# Nrf2460_1.net
KiCad netlist of a schematic drawn in Altium Designer
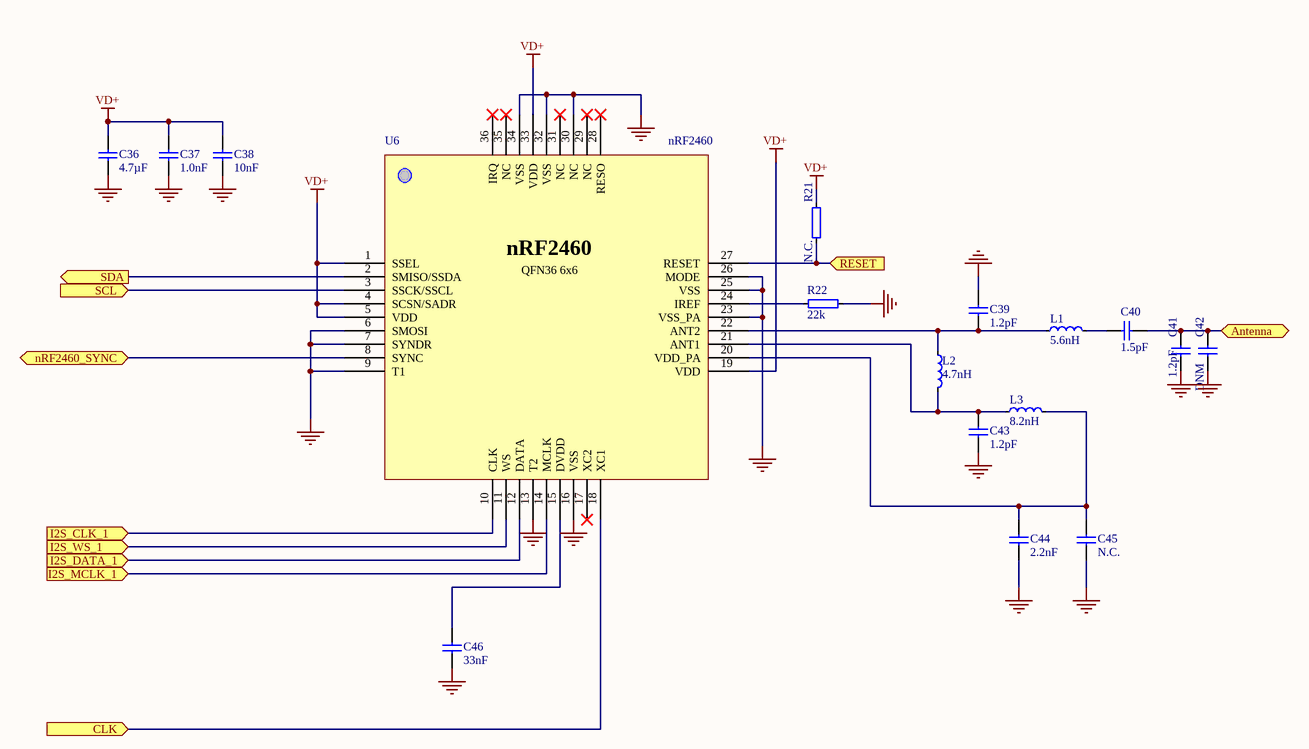
[diagram p0: Nrf2460_1.SchDoc]

(export (version "E")
  (design (tool "Eeschema 10.0.6"))
  (components
    (comp (ref "C36")
      (value "4.7µF")
      (footprint "0805")
      (description "Chip Cap 0805")
      (fields (field (name "PART NUMBER") "C0805-4µ7") (field (name "PUBLISHER") "Nordic Semiconductor"))
      (libsource (lib "Nordic Passive DB") (part "CAP"))
    )
    (comp (ref "C37")
      (value "1.0nF")
      (footprint "0402s")
      (description "Chip Cap 0402")
      (fields (field (name "PART NUMBER") "C0402-1n0") (field (name "PUBLISHER") "Nordic Semiconductor"))
      (libsource (lib "Nordic Passive DB") (part "CAP"))
    )
    (comp (ref "C38")
      (value "10nF")
      (footprint "0402s")
      (description "Chip Cap 0402")
      (fields (field (name "PART NUMBER") "C0402-10n") (field (name "PUBLISHER") "Nordic Semiconductor"))
      (libsource (lib "Nordic Passive DB") (part "CAP"))
    )
    (comp (ref "C39")
      (value "1.2pF")
      (footprint "0402s")
      (description "Chip Cap 0402")
      (fields (field (name "PART NUMBER") "C0402-1.2p") (field (name "PUBLISHER") "Nordic Semiconductor"))
      (libsource (lib "Nordic Passive DB") (part "CAP"))
    )
    (comp (ref "C40")
      (value "1.5pF")
      (footprint "0402s")
      (description "Chip Cap 0402")
      (fields (field (name "PART NUMBER") "C0402-1.5p") (field (name "PUBLISHER") "Nordic Semiconductor"))
      (libsource (lib "Nordic Passive DB") (part "CAP"))
    )
    (comp (ref "C41")
      (value "1.2pF")
      (footprint "0402s")
      (description "Chip Cap 0402")
      (fields (field (name "PART NUMBER") "C0402-1.2p") (field (name "PUBLISHER") "Nordic Semiconductor"))
      (libsource (lib "Nordic Passive DB") (part "CAP"))
    )
    (comp (ref "C42")
      (value "DNM")
      (footprint "0402s")
      (description "Chip Cap 0402")
      (fields (field (name "PART NUMBER") "C0402-1.2p") (field (name "PUBLISHER") "Nordic Semiconductor"))
      (libsource (lib "Nordic Passive DB") (part "CAP"))
    )
    (comp (ref "C43")
      (value "1.2pF")
      (footprint "0402s")
      (description "Chip Cap 0402")
      (fields (field (name "PART NUMBER") "C0402-1.2p") (field (name "PUBLISHER") "Nordic Semiconductor"))
      (libsource (lib "Nordic Passive DB") (part "CAP"))
    )
    (comp (ref "C44")
      (value "2.2nF")
      (footprint "0402s")
      (description "Chip Cap 0402")
      (fields (field (name "PART NUMBER") "C0402-2n2") (field (name "PUBLISHER") "Nordic Semiconductor"))
      (libsource (lib "Nordic Passive DB") (part "CAP"))
    )
    (comp (ref "C45")
      (value "N.C.")
      (footprint "0402s")
      (description "Chip Cap 0402")
      (fields (field (name "PART NUMBER") "C0402-N.C.") (field (name "PUBLISHER") "Nordic Semiconductor"))
      (libsource (lib "Nordic Passive DB") (part "CAP_NO_BOM"))
    )
    (comp (ref "C46")
      (value "33nF")
      (footprint "0402s")
      (description "Chip Cap 0402")
      (fields (field (name "PART NUMBER") "C0402-33n") (field (name "PUBLISHER") "Nordic Semiconductor"))
      (libsource (lib "Nordic Passive DB") (part "CAP"))
    )
    (comp (ref "L1")
      (value "5.6nH")
      (footprint "0402s")
      (description "Chip Ind 0402")
      (fields
        (field (name "PART NUMBER") "L0402-5n6")
        (field (name "MANUFACTURER") "Murata")
        (field (name "PUBLISHER") "Nordic Semiconductor")
      )
      (libsource (lib "Nordic Passive DB") (part "IND"))
    )
    (comp (ref "L2")
      (value "4.7nH")
      (footprint "0402s")
      (description "Chip Ind 0402")
      (fields
        (field (name "PART NUMBER") "L0402-4n7")
        (field (name "MANUFACTURER") "Murata")
        (field (name "PUBLISHER") "Nordic Semiconductor")
      )
      (libsource (lib "Nordic Passive DB") (part "IND"))
    )
    (comp (ref "L3")
      (value "8.2nH")
      (footprint "0402s")
      (description "Chip Ind 0402")
      (fields
        (field (name "PART NUMBER") "L0402-8n2")
        (field (name "MANUFACTURER") "Murata")
        (field (name "PUBLISHER") "Nordic Semiconductor")
      )
      (libsource (lib "Nordic Passive DB") (part "IND"))
    )
    (comp (ref "R21")
      (value "N.C.")
      (footprint "0402s")
      (description "Chip Res 0402")
      (fields (field (name "PART NUMBER") "R0402-N.C.") (field (name "PUBLISHER") "Nordic Semiconductor"))
      (libsource (lib "Nordic Passive DB") (part "RES_1_NO_BOM"))
    )
    (comp (ref "R22")
      (value "22k")
      (footprint "0402s")
      (description "Chip Res 0402")
      (fields (field (name "PART NUMBER") "R0402-22k") (field (name "PUBLISHER") "Nordic Semiconductor"))
      (libsource (lib "Nordic Passive DB") (part "RES_1"))
    )
    (comp (ref "U6")
      (value "nRF2460")
      (footprint "Nordic_QFN36")
      (description "2.4GHz Single Chip Wireless Audio Streamer")
      (fields
        (field (name "MANUFACTURER") "Nordic Semiconductor")
        (field (name "PUBLISHER") "Nordic Semiconductor")
      )
      (libsource (lib "Nordic Active DB") (part "nRF2460"))
    )
  )
  (nets
    (net (code "1") (name "/Antenna") (class "Default")
      (node (ref "C40") (pin "1") (pinfunction "1_1") (pintype "passive"))
      (node (ref "C41") (pin "2") (pinfunction "2_2") (pintype "passive"))
      (node (ref "C42") (pin "2") (pinfunction "2_2") (pintype "passive"))
    )
    (net (code "2") (name "/CLK") (class "Default")
      (node (ref "U6") (pin "18") (pinfunction "XC1_18") (pintype "passive"))
    )
    (net (code "3") (name "/I2S_CLK_1") (class "Default")
      (node (ref "U6") (pin "10") (pinfunction "CLK_10") (pintype "passive"))
    )
    (net (code "4") (name "/I2S_DATA_1") (class "Default")
      (node (ref "U6") (pin "12") (pinfunction "DATA_12") (pintype "passive"))
    )
    (net (code "5") (name "/I2S_MCLK_1") (class "Default")
      (node (ref "U6") (pin "14") (pinfunction "MCLK_14") (pintype "passive"))
    )
    (net (code "6") (name "/I2S_WS_1") (class "Default")
      (node (ref "U6") (pin "11") (pinfunction "WS_11") (pintype "passive"))
    )
    (net (code "7") (name "/RESET") (class "Default")
      (node (ref "R21") (pin "1") (pinfunction "1_1") (pintype "passive"))
      (node (ref "U6") (pin "27") (pinfunction "RESET_27") (pintype "passive"))
    )
    (net (code "8") (name "/SCL") (class "Default")
      (node (ref "U6") (pin "3") (pinfunction "SSCK/SSCL_3") (pintype "passive"))
    )
    (net (code "9") (name "/SDA") (class "Default")
      (node (ref "U6") (pin "2") (pinfunction "SMISO/SSDA_2") (pintype "passive"))
    )
    (net (code "10") (name "/nRF2460_SYNC") (class "Default")
      (node (ref "U6") (pin "8") (pinfunction "SYNC_8") (pintype "passive"))
    )
    (net (code "11") (name "GND") (class "Default")
      (node (ref "C36") (pin "2") (pinfunction "2_2") (pintype "passive"))
      (node (ref "C37") (pin "2") (pinfunction "2_2") (pintype "passive"))
      (node (ref "C38") (pin "2") (pinfunction "2_2") (pintype "passive"))
      (node (ref "C39") (pin "2") (pinfunction "2_2") (pintype "passive"))
      (node (ref "C41") (pin "1") (pinfunction "1_1") (pintype "passive"))
      (node (ref "C42") (pin "1") (pinfunction "1_1") (pintype "passive"))
      (node (ref "C43") (pin "1") (pinfunction "1_1") (pintype "passive"))
      (node (ref "C44") (pin "1") (pinfunction "1_1") (pintype "passive"))
      (node (ref "C45") (pin "1") (pinfunction "1_1") (pintype "passive"))
      (node (ref "C46") (pin "1") (pinfunction "1_1") (pintype "passive"))
      (node (ref "R22") (pin "1") (pinfunction "1_1") (pintype "passive"))
      (node (ref "U6") (pin "13") (pinfunction "T2_13") (pintype "passive"))
      (node (ref "U6") (pin "16") (pinfunction "VSS_16") (pintype "passive"))
      (node (ref "U6") (pin "23") (pinfunction "VSS_PA_23") (pintype "passive"))
      (node (ref "U6") (pin "25") (pinfunction "VSS_25") (pintype "passive"))
      (node (ref "U6") (pin "26") (pinfunction "MODE_26") (pintype "passive"))
      (node (ref "U6") (pin "30") (pinfunction "NC_30") (pintype "passive"))
      (node (ref "U6") (pin "32") (pinfunction "VSS_32") (pintype "passive"))
      (node (ref "U6") (pin "34") (pinfunction "VSS_34") (pintype "passive"))
      (node (ref "U6") (pin "6") (pinfunction "SMOSI_6") (pintype "passive"))
      (node (ref "U6") (pin "7") (pinfunction "SYNDR_7") (pintype "passive"))
      (node (ref "U6") (pin "9") (pinfunction "T1_9") (pintype "passive"))
    )
    (net (code "12") (name "Net-(C40-Pad2)") (class "Default")
      (node (ref "C40") (pin "2") (pinfunction "2_2") (pintype "passive"))
      (node (ref "L1") (pin "2") (pinfunction "2_2") (pintype "passive"))
    )
    (net (code "13") (name "Net-(U6-ANT1)") (class "Default")
      (node (ref "C43") (pin "2") (pinfunction "2_2") (pintype "passive"))
      (node (ref "L2") (pin "2") (pinfunction "2_2") (pintype "passive"))
      (node (ref "L3") (pin "1") (pinfunction "1_1") (pintype "passive"))
      (node (ref "U6") (pin "21") (pinfunction "ANT1_21") (pintype "passive"))
    )
    (net (code "14") (name "Net-(U6-ANT2)") (class "Default")
      (node (ref "C39") (pin "1") (pinfunction "1_1") (pintype "passive"))
      (node (ref "L1") (pin "1") (pinfunction "1_1") (pintype "passive"))
      (node (ref "L2") (pin "1") (pinfunction "1_1") (pintype "passive"))
      (node (ref "U6") (pin "22") (pinfunction "ANT2_22") (pintype "passive"))
    )
    (net (code "15") (name "Net-(U6-DVDD)") (class "Default")
      (node (ref "C46") (pin "2") (pinfunction "2_2") (pintype "passive"))
      (node (ref "U6") (pin "15") (pinfunction "DVDD_15") (pintype "passive"))
    )
    (net (code "16") (name "Net-(U6-IREF)") (class "Default")
      (node (ref "R22") (pin "2") (pinfunction "2_2") (pintype "passive"))
      (node (ref "U6") (pin "24") (pinfunction "IREF_24") (pintype "passive"))
    )
    (net (code "17") (name "Net-(U6-VDD_PA)") (class "Default")
      (node (ref "C44") (pin "2") (pinfunction "2_2") (pintype "passive"))
      (node (ref "C45") (pin "2") (pinfunction "2_2") (pintype "passive"))
      (node (ref "L3") (pin "2") (pinfunction "2_2") (pintype "passive"))
      (node (ref "U6") (pin "20") (pinfunction "VDD_PA_20") (pintype "passive"))
    )
    (net (code "18") (name "VD+") (class "Default")
      (node (ref "C36") (pin "1") (pinfunction "1_1") (pintype "passive"))
      (node (ref "C37") (pin "1") (pinfunction "1_1") (pintype "passive"))
      (node (ref "C38") (pin "1") (pinfunction "1_1") (pintype "passive"))
      (node (ref "R21") (pin "2") (pinfunction "2_2") (pintype "passive"))
      (node (ref "U6") (pin "1") (pinfunction "SSEL_1") (pintype "passive"))
      (node (ref "U6") (pin "19") (pinfunction "VDD_19") (pintype "passive"))
      (node (ref "U6") (pin "33") (pinfunction "VDD_33") (pintype "passive"))
      (node (ref "U6") (pin "4") (pinfunction "SCSN/SADR_4") (pintype "passive"))
      (node (ref "U6") (pin "5") (pinfunction "VDD_5") (pintype "passive"))
    )
    (net (code "19") (name "unconnected-(U6-IRQ-Pad36)") (class "Default")
      (node (ref "U6") (pin "36") (pinfunction "IRQ_36") (pintype "passive+no_connect"))
    )
    (net (code "20") (name "unconnected-(U6-NC-Pad29)") (class "Default")
      (node (ref "U6") (pin "29") (pinfunction "NC_29") (pintype "passive+no_connect"))
    )
    (net (code "21") (name "unconnected-(U6-NC-Pad31)") (class "Default")
      (node (ref "U6") (pin "31") (pinfunction "NC_31") (pintype "passive+no_connect"))
    )
    (net (code "22") (name "unconnected-(U6-NC-Pad35)") (class "Default")
      (node (ref "U6") (pin "35") (pinfunction "NC_35") (pintype "passive+no_connect"))
    )
    (net (code "23") (name "unconnected-(U6-RESO-Pad28)") (class "Default")
      (node (ref "U6") (pin "28") (pinfunction "RESO_28") (pintype "passive+no_connect"))
    )
    (net (code "24") (name "unconnected-(U6-XC2-Pad17)") (class "Default")
      (node (ref "U6") (pin "17") (pinfunction "XC2_17") (pintype "passive+no_connect"))
    )
  )
)
